# DCModuleSplitSupply.net
KiCad netlist of a schematic drawn in EAGLE
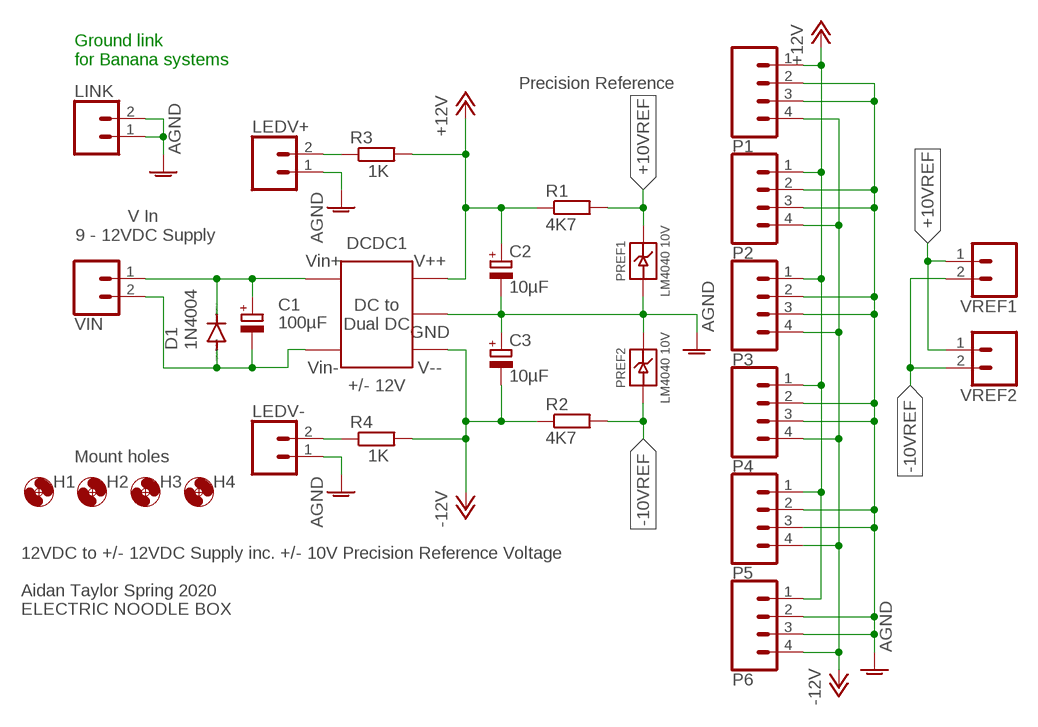
[diagram p0: schematic, sheet 1]

(export (version "E")
  (design (tool "Eeschema 10.0.6"))
  (components
    (comp (ref "C1")
      (value "100µF")
      (footprint "eagle-import:E2,5-6")
      (libsource (lib "eagle-import") (part "CPOL-EUE2.5-6"))
    )
    (comp (ref "C2")
      (value "10µF")
      (footprint "eagle-import:E2-5")
      (libsource (lib "eagle-import") (part "CPOL-EUE2-5"))
    )
    (comp (ref "C3")
      (value "10µF")
      (footprint "eagle-import:E2-5")
      (libsource (lib "eagle-import") (part "CPOL-EUE2-5"))
    )
    (comp (ref "D1")
      (value "1N4004")
      (footprint "eagle-import:DO41-10")
      (libsource (lib "eagle-import") (part "1N4004"))
    )
    (comp (ref "DCDC1")
      (value "+/- 12V")
      (footprint "eagle-import:VRA_ZP-6WR3_SERIES")
      (libsource (lib "eagle-import") (part "VRA1212ZP-6WR3"))
    )
    (comp (ref "H1")
      (value "MOUNT-HOLE3.2")
      (footprint "eagle-import:3,2")
      (libsource (lib "eagle-import") (part "MOUNT-HOLE3.2"))
    )
    (comp (ref "H2")
      (value "MOUNT-HOLE3.2")
      (footprint "eagle-import:3,2")
      (libsource (lib "eagle-import") (part "MOUNT-HOLE3.2"))
    )
    (comp (ref "H3")
      (value "MOUNT-HOLE3.2")
      (footprint "eagle-import:3,2")
      (libsource (lib "eagle-import") (part "MOUNT-HOLE3.2"))
    )
    (comp (ref "H4")
      (value "MOUNT-HOLE3.2")
      (footprint "eagle-import:3,2")
      (libsource (lib "eagle-import") (part "MOUNT-HOLE3.2"))
    )
    (comp (ref "LEDV+")
      (value "2XWIREPAD")
      (footprint "eagle-import:1X02")
      (libsource (lib "eagle-import") (part "2XWIREPAD"))
    )
    (comp (ref "LEDV-")
      (value "2XWIREPAD")
      (footprint "eagle-import:1X02")
      (libsource (lib "eagle-import") (part "2XWIREPAD"))
    )
    (comp (ref "LINK")
      (value "2XWIREPAD")
      (footprint "eagle-import:1X02")
      (libsource (lib "eagle-import") (part "2XWIREPAD"))
    )
    (comp (ref "P1")
      (value "4XMOLEX")
      (footprint "eagle-import:MOLEX-1X4")
      (libsource (lib "eagle-import") (part "4XMOLEX"))
    )
    (comp (ref "P2")
      (value "4XMOLEX")
      (footprint "eagle-import:MOLEX-1X4")
      (libsource (lib "eagle-import") (part "4XMOLEX"))
    )
    (comp (ref "P3")
      (value "4XMOLEX")
      (footprint "eagle-import:MOLEX-1X4")
      (libsource (lib "eagle-import") (part "4XMOLEX"))
    )
    (comp (ref "P4")
      (value "4XMOLEX")
      (footprint "eagle-import:MOLEX-1X4")
      (libsource (lib "eagle-import") (part "4XMOLEX"))
    )
    (comp (ref "P5")
      (value "4XMOLEX")
      (footprint "eagle-import:MOLEX-1X4")
      (libsource (lib "eagle-import") (part "4XMOLEX"))
    )
    (comp (ref "P6")
      (value "4XMOLEX")
      (footprint "eagle-import:MOLEX-1X4")
      (libsource (lib "eagle-import") (part "4XMOLEX"))
    )
    (comp (ref "PREF1")
      (value "LM4040 10V")
      (footprint "eagle-import:TO-92")
      (libsource (lib "eagle-import") (part "LM4040TH"))
    )
    (comp (ref "PREF2")
      (value "LM4040 10V")
      (footprint "eagle-import:TO-92")
      (libsource (lib "eagle-import") (part "LM4040TH"))
    )
    (comp (ref "R1")
      (value "4K7")
      (footprint "eagle-import:0207_10")
      (libsource (lib "eagle-import") (part "R-EU_0207/10"))
    )
    (comp (ref "R2")
      (value "4K7")
      (footprint "eagle-import:0207_10")
      (libsource (lib "eagle-import") (part "R-EU_0207/10"))
    )
    (comp (ref "R3")
      (value "1K")
      (footprint "eagle-import:0207_10")
      (libsource (lib "eagle-import") (part "R-EU_0207/10"))
    )
    (comp (ref "R4")
      (value "1K")
      (footprint "eagle-import:0207_10")
      (libsource (lib "eagle-import") (part "R-EU_0207/10"))
    )
    (comp (ref "VIN")
      (value "2XMOLEX")
      (footprint "eagle-import:MOLEX-1X2")
      (libsource (lib "eagle-import") (part "2XMOLEX"))
    )
    (comp (ref "VREF1")
      (value "2XMOLEX")
      (footprint "eagle-import:MOLEX-1X2")
      (libsource (lib "eagle-import") (part "2XMOLEX"))
    )
    (comp (ref "VREF2")
      (value "2XMOLEX")
      (footprint "eagle-import:MOLEX-1X2")
      (libsource (lib "eagle-import") (part "2XMOLEX"))
    )
  )
  (nets
    (net (code "1") (name "+10VREF") (class "Default")
      (node (ref "PREF1") (pin "2") (pinfunction "CATHODE_2") (pintype "power_in"))
      (node (ref "R1") (pin "2") (pinfunction "2_2") (pintype "passive"))
      (node (ref "VREF1") (pin "1") (pinfunction "1_1") (pintype "passive"))
      (node (ref "VREF2") (pin "1") (pinfunction "1_1") (pintype "passive"))
    )
    (net (code "2") (name "+12V") (class "Default")
      (node (ref "C2") (pin "+") (pinfunction "+_+") (pintype "passive"))
      (node (ref "DCDC1") (pin "VOUT+") (pinfunction "VOUT+_VOUT+") (pintype "bidirectional"))
      (node (ref "P1") (pin "1") (pinfunction "1_1") (pintype "passive"))
      (node (ref "P2") (pin "1") (pinfunction "1_1") (pintype "passive"))
      (node (ref "P3") (pin "1") (pinfunction "1_1") (pintype "passive"))
      (node (ref "P4") (pin "1") (pinfunction "1_1") (pintype "passive"))
      (node (ref "P5") (pin "1") (pinfunction "1_1") (pintype "passive"))
      (node (ref "P6") (pin "1") (pinfunction "1_1") (pintype "passive"))
      (node (ref "R1") (pin "1") (pinfunction "1_1") (pintype "passive"))
      (node (ref "R3") (pin "2") (pinfunction "2_2") (pintype "passive"))
    )
    (net (code "3") (name "-10VREF") (class "Default")
      (node (ref "PREF2") (pin "3") (pinfunction "ANODE_3") (pintype "power_in"))
      (node (ref "R2") (pin "2") (pinfunction "2_2") (pintype "passive"))
      (node (ref "VREF1") (pin "2") (pinfunction "2_2") (pintype "passive"))
      (node (ref "VREF2") (pin "2") (pinfunction "2_2") (pintype "passive"))
    )
    (net (code "4") (name "-12V") (class "Default")
      (node (ref "C3") (pin "-") (pinfunction "-_-") (pintype "passive"))
      (node (ref "DCDC1") (pin "VOUT-") (pinfunction "VOUT-_VOUT-") (pintype "bidirectional"))
      (node (ref "P1") (pin "4") (pinfunction "4_4") (pintype "passive"))
      (node (ref "P2") (pin "4") (pinfunction "4_4") (pintype "passive"))
      (node (ref "P3") (pin "4") (pinfunction "4_4") (pintype "passive"))
      (node (ref "P4") (pin "4") (pinfunction "4_4") (pintype "passive"))
      (node (ref "P5") (pin "4") (pinfunction "4_4") (pintype "passive"))
      (node (ref "P6") (pin "4") (pinfunction "4_4") (pintype "passive"))
      (node (ref "R2") (pin "1") (pinfunction "1_1") (pintype "passive"))
      (node (ref "R4") (pin "2") (pinfunction "2_2") (pintype "passive"))
    )
    (net (code "5") (name "AGND") (class "Default")
      (node (ref "C2") (pin "-") (pinfunction "-_-") (pintype "passive"))
      (node (ref "C3") (pin "+") (pinfunction "+_+") (pintype "passive"))
      (node (ref "DCDC1") (pin "0V") (pinfunction "0V_0V") (pintype "bidirectional"))
      (node (ref "DCDC1") (pin "0V2") (pinfunction "0V_0V2") (pintype "bidirectional"))
      (node (ref "LEDV+") (pin "1") (pinfunction "1_1") (pintype "passive"))
      (node (ref "LEDV-") (pin "1") (pinfunction "1_1") (pintype "passive"))
      (node (ref "LINK") (pin "1") (pinfunction "1_1") (pintype "passive"))
      (node (ref "LINK") (pin "2") (pinfunction "2_2") (pintype "passive"))
      (node (ref "P1") (pin "2") (pinfunction "2_2") (pintype "passive"))
      (node (ref "P1") (pin "3") (pinfunction "3_3") (pintype "passive"))
      (node (ref "P2") (pin "2") (pinfunction "2_2") (pintype "passive"))
      (node (ref "P2") (pin "3") (pinfunction "3_3") (pintype "passive"))
      (node (ref "P3") (pin "2") (pinfunction "2_2") (pintype "passive"))
      (node (ref "P3") (pin "3") (pinfunction "3_3") (pintype "passive"))
      (node (ref "P4") (pin "2") (pinfunction "2_2") (pintype "passive"))
      (node (ref "P4") (pin "3") (pinfunction "3_3") (pintype "passive"))
      (node (ref "P5") (pin "2") (pinfunction "2_2") (pintype "passive"))
      (node (ref "P5") (pin "3") (pinfunction "3_3") (pintype "passive"))
      (node (ref "P6") (pin "2") (pinfunction "2_2") (pintype "passive"))
      (node (ref "P6") (pin "3") (pinfunction "3_3") (pintype "passive"))
      (node (ref "PREF1") (pin "3") (pinfunction "ANODE_3") (pintype "power_in"))
      (node (ref "PREF2") (pin "2") (pinfunction "CATHODE_2") (pintype "power_in"))
    )
    (net (code "6") (name "Net-(C1-Pad+)") (class "Default")
      (node (ref "C1") (pin "+") (pinfunction "+_+") (pintype "passive"))
      (node (ref "D1") (pin "C") (pinfunction "C_C") (pintype "passive"))
      (node (ref "DCDC1") (pin "VIN") (pinfunction "VIN+_VIN") (pintype "bidirectional"))
      (node (ref "DCDC1") (pin "VIN2") (pinfunction "VIN+_VIN2") (pintype "bidirectional"))
      (node (ref "VIN") (pin "1") (pinfunction "1_1") (pintype "passive"))
    )
    (net (code "7") (name "Net-(C1-Pad-)") (class "Default")
      (node (ref "C1") (pin "-") (pinfunction "-_-") (pintype "passive"))
      (node (ref "D1") (pin "A") (pinfunction "A_A") (pintype "passive"))
      (node (ref "DCDC1") (pin "GND") (pinfunction "VIN-_GND") (pintype "bidirectional"))
      (node (ref "DCDC1") (pin "GND2") (pinfunction "VIN-_GND2") (pintype "bidirectional"))
      (node (ref "VIN") (pin "2") (pinfunction "2_2") (pintype "passive"))
    )
    (net (code "8") (name "Net-(LEDV+-Pad2)") (class "Default")
      (node (ref "LEDV+") (pin "2") (pinfunction "2_2") (pintype "passive"))
      (node (ref "R3") (pin "1") (pinfunction "1_1") (pintype "passive"))
    )
    (net (code "9") (name "Net-(LEDV--Pad2)") (class "Default")
      (node (ref "LEDV-") (pin "2") (pinfunction "2_2") (pintype "passive"))
      (node (ref "R4") (pin "1") (pinfunction "1_1") (pintype "passive"))
    )
  )
)
